# inhaler.net
KiCad netlist of a schematic drawn in EAGLE
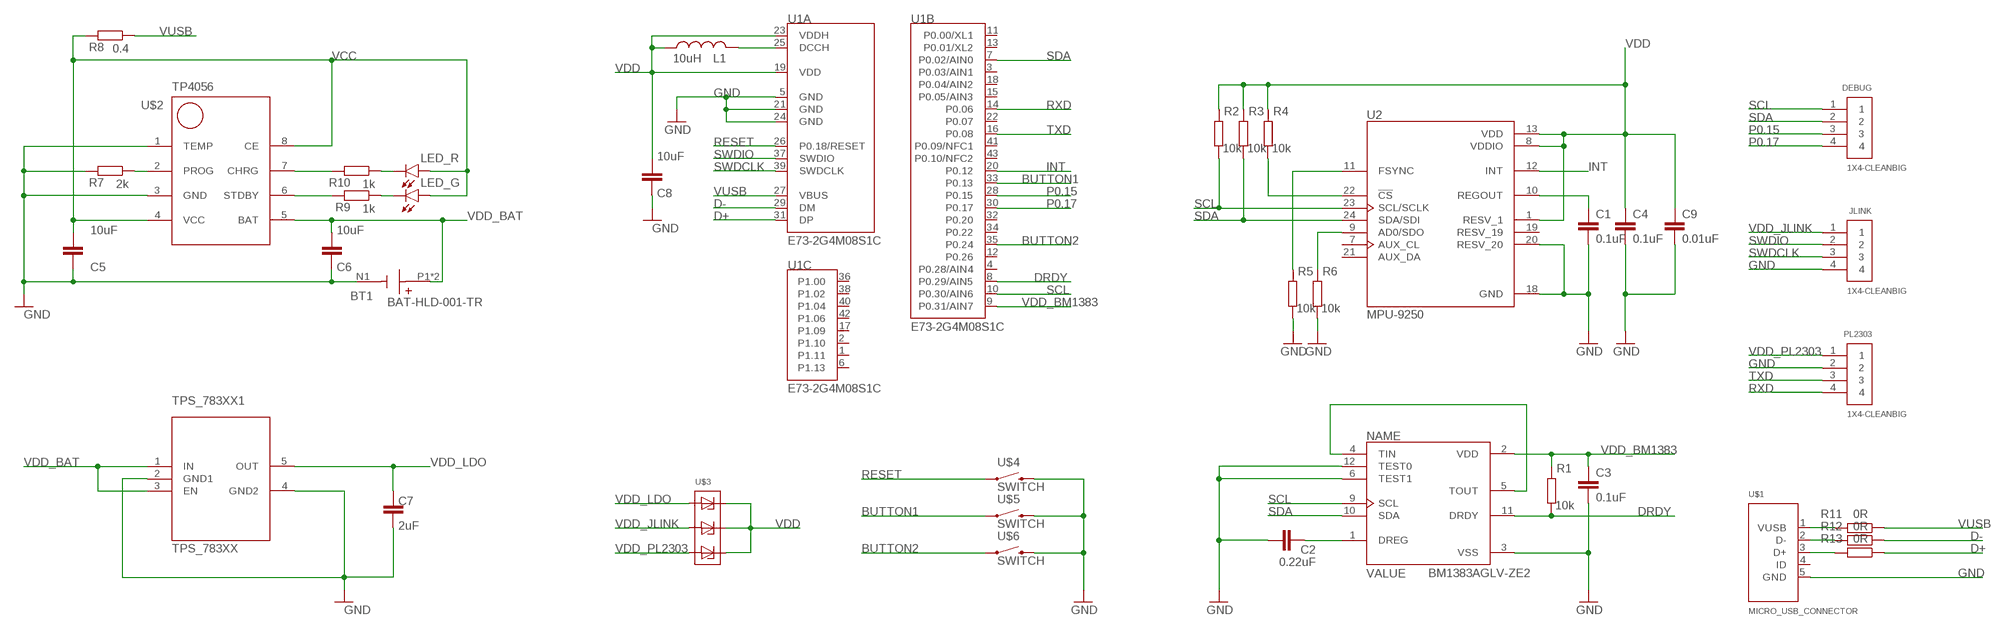
[diagram p0: schematic, sheet 1]

(export (version "E")
  (design (tool "Eeschema 10.0.6"))
  (components
    (comp (ref "BT1")
      (value "BAT-HLD-001-TR")
      (footprint "eagle-import:BAT_BAT-HLD-001-TR")
      (fields (field (name "MF") "Linx"))
      (libsource (lib "eagle-import") (part "BAT-HLD-001-TR"))
    )
    (comp (ref "C1")
      (value "0.1uF")
      (footprint "eagle-import:C0805")
      (fields (field (name "POPULARITY") "0.1u"))
      (libsource (lib "eagle-import") (part "C-EUC0805"))
    )
    (comp (ref "C2")
      (value "0.22uF")
      (footprint "eagle-import:C0805")
      (libsource (lib "eagle-import") (part "C-EUC0805"))
    )
    (comp (ref "C3")
      (value "0.1uF")
      (footprint "eagle-import:C0805")
      (libsource (lib "eagle-import") (part "C-EUC0805"))
    )
    (comp (ref "C4")
      (value "0.1uF")
      (footprint "eagle-import:C0805")
      (fields (field (name "POPULARITY") "0.1u"))
      (libsource (lib "eagle-import") (part "C-EUC0805"))
    )
    (comp (ref "C5")
      (value "10uF")
      (footprint "eagle-import:C0805")
      (libsource (lib "eagle-import") (part "C-EUC0805"))
    )
    (comp (ref "C6")
      (value "10uF")
      (footprint "eagle-import:C0805")
      (libsource (lib "eagle-import") (part "C-EUC0805"))
    )
    (comp (ref "C7")
      (value "2uF")
      (footprint "eagle-import:C0805")
      (libsource (lib "eagle-import") (part "C-EUC0805"))
    )
    (comp (ref "C8")
      (value "10uF")
      (footprint "eagle-import:C0805")
      (libsource (lib "eagle-import") (part "C-EUC0805"))
    )
    (comp (ref "C9")
      (value "0.01uF")
      (footprint "eagle-import:C0805")
      (fields (field (name "POPULARITY") "0.1u"))
      (libsource (lib "eagle-import") (part "C-EUC0805"))
    )
    (comp (ref "DEBUG")
      (value "1X4-CLEANBIG")
      (footprint "eagle-import:1X04-CLEANBIG")
      (libsource (lib "eagle-import") (part "1X4-CLEANBIG"))
    )
    (comp (ref "JLINK")
      (value "1X4-CLEANBIG")
      (footprint "eagle-import:1X04-CLEANBIG")
      (libsource (lib "eagle-import") (part "1X4-CLEANBIG"))
    )
    (comp (ref "L1")
      (value "10uH")
      (footprint "eagle-import:L0805")
      (libsource (lib "eagle-import") (part "L-USL0805"))
    )
    (comp (ref "LED_G")
      (value "LEDSMT1206")
      (footprint "eagle-import:1206")
      (libsource (lib "eagle-import") (part "LEDSMT1206"))
    )
    (comp (ref "LED_R")
      (value "LEDSMT1206")
      (footprint "eagle-import:1206")
      (libsource (lib "eagle-import") (part "LEDSMT1206"))
    )
    (comp (ref "PL2303")
      (value "1X4-CLEANBIG")
      (footprint "eagle-import:1X04-CLEANBIG")
      (libsource (lib "eagle-import") (part "1X4-CLEANBIG"))
    )
    (comp (ref "R1")
      (value "10k")
      (footprint "eagle-import:R0805")
      (libsource (lib "eagle-import") (part "R-EU_R0805"))
    )
    (comp (ref "R2")
      (value "10k")
      (footprint "eagle-import:R0805")
      (libsource (lib "eagle-import") (part "R-EU_R0805"))
    )
    (comp (ref "R3")
      (value "10k")
      (footprint "eagle-import:R0805")
      (libsource (lib "eagle-import") (part "R-EU_R0805"))
    )
    (comp (ref "R4")
      (value "10k")
      (footprint "eagle-import:R0805")
      (libsource (lib "eagle-import") (part "R-EU_R0805"))
    )
    (comp (ref "R5")
      (value "10k")
      (footprint "eagle-import:R0805")
      (libsource (lib "eagle-import") (part "R-EU_R0805"))
    )
    (comp (ref "R6")
      (value "10k")
      (footprint "eagle-import:R0805")
      (libsource (lib "eagle-import") (part "R-EU_R0805"))
    )
    (comp (ref "R7")
      (value "2k")
      (footprint "eagle-import:R0805")
      (libsource (lib "eagle-import") (part "R-EU_R0805"))
    )
    (comp (ref "R8")
      (value "0.4")
      (footprint "eagle-import:R0805")
      (libsource (lib "eagle-import") (part "R-EU_R0805"))
    )
    (comp (ref "R9")
      (value "1k")
      (footprint "eagle-import:R0805")
      (libsource (lib "eagle-import") (part "R-EU_R0805"))
    )
    (comp (ref "R10")
      (value "1k")
      (footprint "eagle-import:R0805")
      (libsource (lib "eagle-import") (part "R-EU_R0805"))
    )
    (comp (ref "R11")
      (value "0R")
      (footprint "eagle-import:R0805")
      (libsource (lib "eagle-import") (part "R-EU_R0805"))
    )
    (comp (ref "R12")
      (value "0R")
      (footprint "eagle-import:R0805")
      (libsource (lib "eagle-import") (part "R-EU_R0805"))
    )
    (comp (ref "R13")
      (value "0R")
      (footprint "eagle-import:R0805")
      (libsource (lib "eagle-import") (part "R-EU_R0805"))
    )
    (comp (ref "TPS_783XX1")
      (value "TPS_783XX")
      (footprint "eagle-import:SOT65P280X145-5N")
      (libsource (lib "eagle-import") (part "TPS_783XX"))
    )
    (comp (ref "U$1")
      (value "MICRO_USB_CONNECTOR")
      (footprint "eagle-import:MICRO_USB_4LEGS")
      (libsource (lib "eagle-import") (part "MICRO_USB_CONNECTOR"))
    )
    (comp (ref "U$2")
      (value "TP4056")
      (footprint "eagle-import:SOP8")
      (libsource (lib "eagle-import") (part "TP4056"))
    )
    (comp (ref "U$3")
      (value "SD103ATW")
      (footprint "eagle-import:SOT363")
      (libsource (lib "eagle-import") (part "SD103ATW"))
    )
    (comp (ref "U$4")
      (value "SWITCH")
      (footprint "eagle-import:SWITCH_2PIN")
      (libsource (lib "eagle-import") (part "SWITCH"))
    )
    (comp (ref "U$5")
      (value "SWITCH")
      (footprint "eagle-import:SWITCH_2PIN")
      (libsource (lib "eagle-import") (part "SWITCH"))
    )
    (comp (ref "U$6")
      (value "SWITCH")
      (footprint "eagle-import:SWITCH_2PIN")
      (libsource (lib "eagle-import") (part "SWITCH"))
    )
    (comp (ref "U1")
      (value "E73-2G4M08S1C")
      (footprint "eagle-import:E73-2G4M08S1C")
      (fields (field (name "MF") "EBYTE"))
      (libsource (lib "eagle-import") (part "E73-2G4M08S1C"))
    )
    (comp (ref "U2")
      (value "MPU-9250")
      (footprint "eagle-import:QFN40P300X300X105-24N")
      (fields (field (name "MF") "TDK InvenSense"))
      (libsource (lib "eagle-import") (part "MPU-9250"))
    )
    (comp (ref "U3")
      (value "BM1383AGLV-ZE2")
      (footprint "eagle-import:PQFN55P250X250X100-12N")
      (fields (field (name "MF") "Rohm") (field (name "MP") "BM1383AGLV-ZE2"))
      (libsource (lib "eagle-import") (part "BM1383AGLV-ZE2"))
    )
  )
  (nets
    (net (code "1") (name "/BUTTON1") (class "Default")
      (node (ref "U$5") (pin "1") (pinfunction "1_1") (pintype "passive"))
      (node (ref "U1") (pin "33") (pinfunction "P0.13_33") (pintype "bidirectional"))
    )
    (net (code "2") (name "/BUTTON2") (class "Default")
      (node (ref "U$6") (pin "1") (pinfunction "1_1") (pintype "passive"))
      (node (ref "U1") (pin "35") (pinfunction "P0.24_35") (pintype "bidirectional"))
    )
    (net (code "3") (name "/D+") (class "Default")
      (node (ref "R13") (pin "1") (pinfunction "1_1") (pintype "passive"))
      (node (ref "U1") (pin "31") (pinfunction "DP_31") (pintype "bidirectional"))
    )
    (net (code "4") (name "/D-") (class "Default")
      (node (ref "R12") (pin "1") (pinfunction "1_1") (pintype "passive"))
      (node (ref "U1") (pin "29") (pinfunction "DM_29") (pintype "bidirectional"))
    )
    (net (code "5") (name "/DRDY") (class "Default")
      (node (ref "R1") (pin "1") (pinfunction "1_1") (pintype "passive"))
      (node (ref "U1") (pin "8") (pinfunction "P0.29/AIN5_8") (pintype "bidirectional"))
      (node (ref "U3") (pin "11") (pinfunction "DRDY_11") (pintype "output"))
    )
    (net (code "6") (name "/INT") (class "Default")
      (node (ref "U1") (pin "20") (pinfunction "P0.12_20") (pintype "bidirectional"))
      (node (ref "U2") (pin "12") (pinfunction "INT_12") (pintype "output"))
    )
    (net (code "7") (name "/P0.15") (class "Default")
      (node (ref "DEBUG") (pin "3") (pinfunction "3_3") (pintype "bidirectional"))
      (node (ref "U1") (pin "28") (pinfunction "P0.15_28") (pintype "bidirectional"))
    )
    (net (code "8") (name "/P0.17") (class "Default")
      (node (ref "DEBUG") (pin "4") (pinfunction "4_4") (pintype "bidirectional"))
      (node (ref "U1") (pin "30") (pinfunction "P0.17_30") (pintype "bidirectional"))
    )
    (net (code "9") (name "/RESET") (class "Default")
      (node (ref "U$4") (pin "1") (pinfunction "1_1") (pintype "passive"))
      (node (ref "U1") (pin "26") (pinfunction "P0.18/RESET_26") (pintype "bidirectional"))
    )
    (net (code "10") (name "/RXD") (class "Default")
      (node (ref "PL2303") (pin "4") (pinfunction "4_4") (pintype "bidirectional"))
      (node (ref "U1") (pin "14") (pinfunction "P0.06_14") (pintype "bidirectional"))
    )
    (net (code "11") (name "/SCL") (class "Default")
      (node (ref "DEBUG") (pin "1") (pinfunction "1_1") (pintype "bidirectional"))
      (node (ref "R2") (pin "1") (pinfunction "1_1") (pintype "passive"))
      (node (ref "U1") (pin "10") (pinfunction "P0.30/AIN6_10") (pintype "bidirectional"))
      (node (ref "U2") (pin "23") (pinfunction "SCL/SCLK_23") (pintype "input"))
      (node (ref "U3") (pin "9") (pinfunction "SCL_9") (pintype "input"))
    )
    (net (code "12") (name "/SDA") (class "Default")
      (node (ref "DEBUG") (pin "2") (pinfunction "2_2") (pintype "bidirectional"))
      (node (ref "R3") (pin "1") (pinfunction "1_1") (pintype "passive"))
      (node (ref "U1") (pin "7") (pinfunction "P0.02/AIN0_7") (pintype "bidirectional"))
      (node (ref "U2") (pin "24") (pinfunction "SDA/SDI_24") (pintype "bidirectional"))
      (node (ref "U3") (pin "10") (pinfunction "SDA_10") (pintype "bidirectional"))
    )
    (net (code "13") (name "/SWDCLK") (class "Default")
      (node (ref "JLINK") (pin "3") (pinfunction "3_3") (pintype "bidirectional"))
      (node (ref "U1") (pin "39") (pinfunction "SWDCLK_39") (pintype "bidirectional"))
    )
    (net (code "14") (name "/SWDIO") (class "Default")
      (node (ref "JLINK") (pin "2") (pinfunction "2_2") (pintype "bidirectional"))
      (node (ref "U1") (pin "37") (pinfunction "SWDIO_37") (pintype "bidirectional"))
    )
    (net (code "15") (name "/TXD") (class "Default")
      (node (ref "PL2303") (pin "3") (pinfunction "3_3") (pintype "bidirectional"))
      (node (ref "U1") (pin "16") (pinfunction "P0.08_16") (pintype "bidirectional"))
    )
    (net (code "16") (name "/VCC") (class "Default")
      (node (ref "C5") (pin "2") (pinfunction "2_2") (pintype "passive"))
      (node (ref "LED_G") (pin "A") (pinfunction "A_A") (pintype "passive"))
      (node (ref "LED_R") (pin "A") (pinfunction "A_A") (pintype "passive"))
      (node (ref "R8") (pin "2") (pinfunction "2_2") (pintype "passive"))
      (node (ref "U$2") (pin "4") (pinfunction "VCC_4") (pintype "bidirectional"))
      (node (ref "U$2") (pin "8") (pinfunction "CE_8") (pintype "bidirectional"))
    )
    (net (code "17") (name "/VDD") (class "Default")
      (node (ref "C4") (pin "1") (pinfunction "1_1") (pintype "passive"))
      (node (ref "C8") (pin "2") (pinfunction "2_2") (pintype "passive"))
      (node (ref "C9") (pin "1") (pinfunction "1_1") (pintype "passive"))
      (node (ref "L1") (pin "1") (pinfunction "1_1") (pintype "passive"))
      (node (ref "R2") (pin "2") (pinfunction "2_2") (pintype "passive"))
      (node (ref "R3") (pin "2") (pinfunction "2_2") (pintype "passive"))
      (node (ref "R4") (pin "2") (pinfunction "2_2") (pintype "passive"))
      (node (ref "U$3") (pin "2") (pinfunction "2_2") (pintype "bidirectional"))
      (node (ref "U$3") (pin "4") (pinfunction "4_4") (pintype "bidirectional"))
      (node (ref "U$3") (pin "6") (pinfunction "6_6") (pintype "bidirectional"))
      (node (ref "U1") (pin "19") (pinfunction "VDD_19") (pintype "bidirectional"))
      (node (ref "U1") (pin "23") (pinfunction "VDDH_23") (pintype "bidirectional"))
      (node (ref "U2") (pin "1") (pinfunction "RESV_1_1") (pintype "passive"))
      (node (ref "U2") (pin "13") (pinfunction "VDD_13") (pintype "power_in"))
      (node (ref "U2") (pin "8") (pinfunction "VDDIO_8") (pintype "power_in"))
    )
    (net (code "18") (name "/VDD_BAT") (class "Default")
      (node (ref "BT1") (pin "P1") (pinfunction "+_P1") (pintype "passive"))
      (node (ref "BT1") (pin "P2") (pinfunction "+_P2") (pintype "passive"))
      (node (ref "C6") (pin "2") (pinfunction "2_2") (pintype "passive"))
      (node (ref "TPS_783XX1") (pin "1") (pinfunction "IN_1") (pintype "bidirectional"))
      (node (ref "TPS_783XX1") (pin "3") (pinfunction "EN_3") (pintype "bidirectional"))
      (node (ref "U$2") (pin "5") (pinfunction "BAT_5") (pintype "bidirectional"))
    )
    (net (code "19") (name "/VDD_BM1383") (class "Default")
      (node (ref "C3") (pin "1") (pinfunction "1_1") (pintype "passive"))
      (node (ref "R1") (pin "2") (pinfunction "2_2") (pintype "passive"))
      (node (ref "U1") (pin "9") (pinfunction "P0.31/AIN7_9") (pintype "bidirectional"))
      (node (ref "U3") (pin "2") (pinfunction "VDD_2") (pintype "power_in"))
    )
    (net (code "20") (name "/VDD_JLINK") (class "Default")
      (node (ref "JLINK") (pin "1") (pinfunction "1_1") (pintype "bidirectional"))
      (node (ref "U$3") (pin "3") (pinfunction "3_3") (pintype "bidirectional"))
    )
    (net (code "21") (name "/VDD_LDO") (class "Default")
      (node (ref "C7") (pin "2") (pinfunction "2_2") (pintype "passive"))
      (node (ref "TPS_783XX1") (pin "5") (pinfunction "OUT_5") (pintype "bidirectional"))
      (node (ref "U$3") (pin "1") (pinfunction "1_1") (pintype "bidirectional"))
    )
    (net (code "22") (name "/VDD_PL2303") (class "Default")
      (node (ref "PL2303") (pin "1") (pinfunction "1_1") (pintype "bidirectional"))
      (node (ref "U$3") (pin "5") (pinfunction "5_5") (pintype "bidirectional"))
    )
    (net (code "23") (name "/VUSB") (class "Default")
      (node (ref "R11") (pin "1") (pinfunction "1_1") (pintype "passive"))
      (node (ref "R8") (pin "1") (pinfunction "1_1") (pintype "passive"))
      (node (ref "U1") (pin "27") (pinfunction "VBUS_27") (pintype "bidirectional"))
    )
    (net (code "24") (name "GND") (class "Default")
      (node (ref "BT1") (pin "N1") (pinfunction "-_N1") (pintype "passive"))
      (node (ref "C1") (pin "2") (pinfunction "2_2") (pintype "passive"))
      (node (ref "C2") (pin "1") (pinfunction "1_1") (pintype "passive"))
      (node (ref "C3") (pin "2") (pinfunction "2_2") (pintype "passive"))
      (node (ref "C4") (pin "2") (pinfunction "2_2") (pintype "passive"))
      (node (ref "C5") (pin "1") (pinfunction "1_1") (pintype "passive"))
      (node (ref "C6") (pin "1") (pinfunction "1_1") (pintype "passive"))
      (node (ref "C7") (pin "1") (pinfunction "1_1") (pintype "passive"))
      (node (ref "C8") (pin "1") (pinfunction "1_1") (pintype "passive"))
      (node (ref "C9") (pin "2") (pinfunction "2_2") (pintype "passive"))
      (node (ref "JLINK") (pin "4") (pinfunction "4_4") (pintype "bidirectional"))
      (node (ref "PL2303") (pin "2") (pinfunction "2_2") (pintype "bidirectional"))
      (node (ref "R5") (pin "1") (pinfunction "1_1") (pintype "passive"))
      (node (ref "R6") (pin "1") (pinfunction "1_1") (pintype "passive"))
      (node (ref "R7") (pin "2") (pinfunction "2_2") (pintype "passive"))
      (node (ref "TPS_783XX1") (pin "2") (pinfunction "GND1_2") (pintype "bidirectional"))
      (node (ref "TPS_783XX1") (pin "4") (pinfunction "GND2_4") (pintype "bidirectional"))
      (node (ref "U$1") (pin "5") (pinfunction "GND_5") (pintype "bidirectional"))
      (node (ref "U$2") (pin "1") (pinfunction "TEMP_1") (pintype "bidirectional"))
      (node (ref "U$2") (pin "3") (pinfunction "GND_3") (pintype "bidirectional"))
      (node (ref "U$4") (pin "2") (pinfunction "2_2") (pintype "passive"))
      (node (ref "U$5") (pin "2") (pinfunction "2_2") (pintype "passive"))
      (node (ref "U$6") (pin "2") (pinfunction "2_2") (pintype "passive"))
      (node (ref "U1") (pin "21") (pinfunction "GND_21") (pintype "bidirectional"))
      (node (ref "U1") (pin "24") (pinfunction "GND_24") (pintype "bidirectional"))
      (node (ref "U1") (pin "5") (pinfunction "GND_5") (pintype "bidirectional"))
      (node (ref "U2") (pin "18") (pinfunction "GND_18") (pintype "power_in"))
      (node (ref "U2") (pin "20") (pinfunction "RESV_20_20") (pintype "passive"))
      (node (ref "U3") (pin "12") (pinfunction "TEST0_12") (pintype "input"))
      (node (ref "U3") (pin "3") (pinfunction "VSS_3") (pintype "power_in"))
      (node (ref "U3") (pin "6") (pinfunction "TEST1_6") (pintype "input"))
    )
    (net (code "25") (name "Net-(LED_G-PadC)") (class "Default")
      (node (ref "LED_G") (pin "C") (pinfunction "C_C") (pintype "passive"))
      (node (ref "R9") (pin "1") (pinfunction "1_1") (pintype "passive"))
    )
    (net (code "26") (name "Net-(LED_R-PadC)") (class "Default")
      (node (ref "LED_R") (pin "C") (pinfunction "C_C") (pintype "passive"))
      (node (ref "R10") (pin "1") (pinfunction "1_1") (pintype "passive"))
    )
    (net (code "27") (name "Net-(U$1-D+)") (class "Default")
      (node (ref "R13") (pin "2") (pinfunction "2_2") (pintype "passive"))
      (node (ref "U$1") (pin "3") (pinfunction "D+_3") (pintype "bidirectional"))
    )
    (net (code "28") (name "Net-(U$1-D-)") (class "Default")
      (node (ref "R12") (pin "2") (pinfunction "2_2") (pintype "passive"))
      (node (ref "U$1") (pin "2") (pinfunction "D-_2") (pintype "bidirectional"))
    )
    (net (code "29") (name "Net-(U$1-VUSB)") (class "Default")
      (node (ref "R11") (pin "2") (pinfunction "2_2") (pintype "passive"))
      (node (ref "U$1") (pin "1") (pinfunction "VUSB_1") (pintype "bidirectional"))
    )
    (net (code "30") (name "Net-(U$2-CHRG)") (class "Default")
      (node (ref "R10") (pin "2") (pinfunction "2_2") (pintype "passive"))
      (node (ref "U$2") (pin "7") (pinfunction "CHRG_7") (pintype "bidirectional"))
    )
    (net (code "31") (name "Net-(U$2-PROG)") (class "Default")
      (node (ref "R7") (pin "1") (pinfunction "1_1") (pintype "passive"))
      (node (ref "U$2") (pin "2") (pinfunction "PROG_2") (pintype "bidirectional"))
    )
    (net (code "32") (name "Net-(U$2-STDBY)") (class "Default")
      (node (ref "R9") (pin "2") (pinfunction "2_2") (pintype "passive"))
      (node (ref "U$2") (pin "6") (pinfunction "STDBY_6") (pintype "bidirectional"))
    )
    (net (code "33") (name "Net-(U1A-DCCH)") (class "Default")
      (node (ref "L1") (pin "2") (pinfunction "2_2") (pintype "passive"))
      (node (ref "U1") (pin "25") (pinfunction "DCCH_25") (pintype "bidirectional"))
    )
    (net (code "34") (name "Net-(U2-AD0{slash}SDO)") (class "Default")
      (node (ref "R6") (pin "2") (pinfunction "2_2") (pintype "passive"))
      (node (ref "U2") (pin "9") (pinfunction "AD0/SDO_9") (pintype "output"))
    )
    (net (code "35") (name "Net-(U2-FSYNC)") (class "Default")
      (node (ref "R5") (pin "2") (pinfunction "2_2") (pintype "passive"))
      (node (ref "U2") (pin "11") (pinfunction "FSYNC_11") (pintype "input"))
    )
    (net (code "36") (name "Net-(U2-REGOUT)") (class "Default")
      (node (ref "C1") (pin "1") (pinfunction "1_1") (pintype "passive"))
      (node (ref "U2") (pin "10") (pinfunction "REGOUT_10") (pintype "output"))
    )
    (net (code "37") (name "Net-(U2-~{CS})") (class "Default")
      (node (ref "R4") (pin "1") (pinfunction "1_1") (pintype "passive"))
      (node (ref "U2") (pin "22") (pinfunction "~{CS}_22") (pintype "input"))
    )
    (net (code "38") (name "Net-(U3-DREG)") (class "Default")
      (node (ref "C2") (pin "2") (pinfunction "2_2") (pintype "passive"))
      (node (ref "U3") (pin "1") (pinfunction "DREG_1") (pintype "passive"))
    )
    (net (code "39") (name "Net-(U3-TIN)") (class "Default")
      (node (ref "U3") (pin "4") (pinfunction "TIN_4") (pintype "input"))
      (node (ref "U3") (pin "5") (pinfunction "TOUT_5") (pintype "output"))
    )
    (net (code "40") (name "unconnected-(U$1-ID-Pad4)") (class "Default")
      (node (ref "U$1") (pin "4") (pinfunction "ID_4") (pintype "bidirectional"))
    )
    (net (code "41") (name "unconnected-(U1B-P0.00{slash}XL1-Pad11)") (class "Default")
      (node (ref "U1") (pin "11") (pinfunction "P0.00/XL1_11") (pintype "bidirectional"))
    )
    (net (code "42") (name "unconnected-(U1B-P0.01{slash}XL2-Pad13)") (class "Default")
      (node (ref "U1") (pin "13") (pinfunction "P0.01/XL2_13") (pintype "bidirectional"))
    )
    (net (code "43") (name "unconnected-(U1B-P0.03{slash}AIN1-Pad3)") (class "Default")
      (node (ref "U1") (pin "3") (pinfunction "P0.03/AIN1_3") (pintype "bidirectional"))
    )
    (net (code "44") (name "unconnected-(U1B-P0.04{slash}AIN2-Pad18)") (class "Default")
      (node (ref "U1") (pin "18") (pinfunction "P0.04/AIN2_18") (pintype "bidirectional"))
    )
    (net (code "45") (name "unconnected-(U1B-P0.05{slash}AIN3-Pad15)") (class "Default")
      (node (ref "U1") (pin "15") (pinfunction "P0.05/AIN3_15") (pintype "bidirectional"))
    )
    (net (code "46") (name "unconnected-(U1B-P0.07-Pad22)") (class "Default")
      (node (ref "U1") (pin "22") (pinfunction "P0.07_22") (pintype "bidirectional"))
    )
    (net (code "47") (name "unconnected-(U1B-P0.09{slash}NFC1-Pad41)") (class "Default")
      (node (ref "U1") (pin "41") (pinfunction "P0.09/NFC1_41") (pintype "bidirectional"))
    )
    (net (code "48") (name "unconnected-(U1B-P0.10{slash}NFC2-Pad43)") (class "Default")
      (node (ref "U1") (pin "43") (pinfunction "P0.10/NFC2_43") (pintype "bidirectional"))
    )
    (net (code "49") (name "unconnected-(U1B-P0.20-Pad32)") (class "Default")
      (node (ref "U1") (pin "32") (pinfunction "P0.20_32") (pintype "bidirectional"))
    )
    (net (code "50") (name "unconnected-(U1B-P0.22-Pad34)") (class "Default")
      (node (ref "U1") (pin "34") (pinfunction "P0.22_34") (pintype "bidirectional"))
    )
    (net (code "51") (name "unconnected-(U1B-P0.26-Pad12)") (class "Default")
      (node (ref "U1") (pin "12") (pinfunction "P0.26_12") (pintype "bidirectional"))
    )
    (net (code "52") (name "unconnected-(U1B-P0.28{slash}AIN4-Pad4)") (class "Default")
      (node (ref "U1") (pin "4") (pinfunction "P0.28/AIN4_4") (pintype "bidirectional"))
    )
    (net (code "53") (name "unconnected-(U1C-P1.00-Pad36)") (class "Default")
      (node (ref "U1") (pin "36") (pinfunction "P1.00_36") (pintype "bidirectional"))
    )
    (net (code "54") (name "unconnected-(U1C-P1.02-Pad38)") (class "Default")
      (node (ref "U1") (pin "38") (pinfunction "P1.02_38") (pintype "bidirectional"))
    )
    (net (code "55") (name "unconnected-(U1C-P1.04-Pad40)") (class "Default")
      (node (ref "U1") (pin "40") (pinfunction "P1.04_40") (pintype "bidirectional"))
    )
    (net (code "56") (name "unconnected-(U1C-P1.06-Pad42)") (class "Default")
      (node (ref "U1") (pin "42") (pinfunction "P1.06_42") (pintype "bidirectional"))
    )
    (net (code "57") (name "unconnected-(U1C-P1.09-Pad17)") (class "Default")
      (node (ref "U1") (pin "17") (pinfunction "P1.09_17") (pintype "bidirectional"))
    )
    (net (code "58") (name "unconnected-(U1C-P1.10-Pad2)") (class "Default")
      (node (ref "U1") (pin "2") (pinfunction "P1.10_2") (pintype "bidirectional"))
    )
    (net (code "59") (name "unconnected-(U1C-P1.11-Pad1)") (class "Default")
      (node (ref "U1") (pin "1") (pinfunction "P1.11_1") (pintype "bidirectional"))
    )
    (net (code "60") (name "unconnected-(U1C-P1.13-Pad6)") (class "Default")
      (node (ref "U1") (pin "6") (pinfunction "P1.13_6") (pintype "bidirectional"))
    )
    (net (code "61") (name "unconnected-(U2-AUX_CL-Pad7)") (class "Default")
      (node (ref "U2") (pin "7") (pinfunction "AUX_CL_7") (pintype "input"))
    )
    (net (code "62") (name "unconnected-(U2-AUX_DA-Pad21)") (class "Default")
      (node (ref "U2") (pin "21") (pinfunction "AUX_DA_21") (pintype "input"))
    )
    (net (code "63") (name "unconnected-(U2-RESV_19-Pad19)") (class "Default")
      (node (ref "U2") (pin "19") (pinfunction "RESV_19_19") (pintype "passive"))
    )
  )
)
